# psu_testboard_v1_1_1.net
KiCad netlist of a schematic drawn in EAGLE
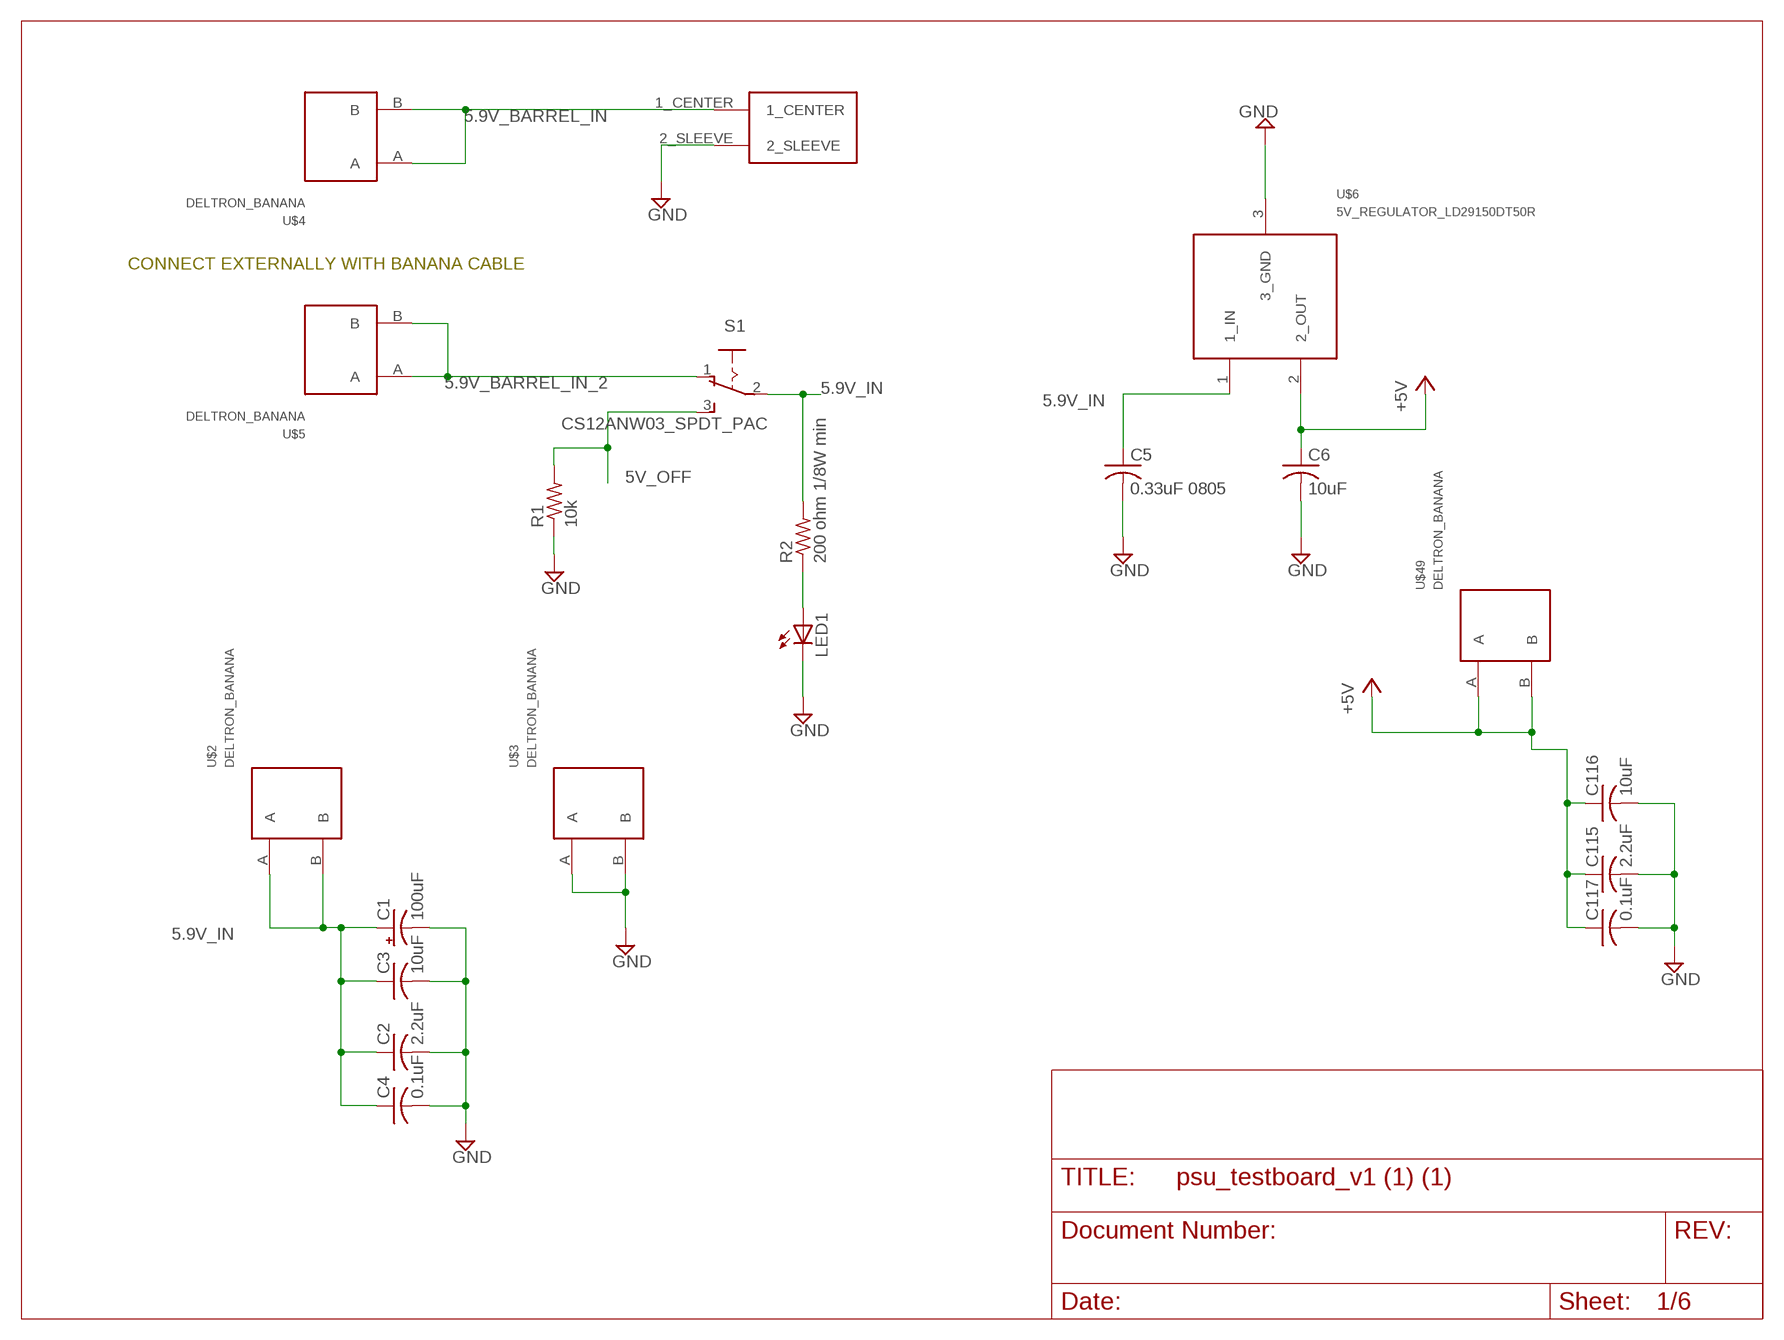
[diagram p0: schematic, sheet 1]
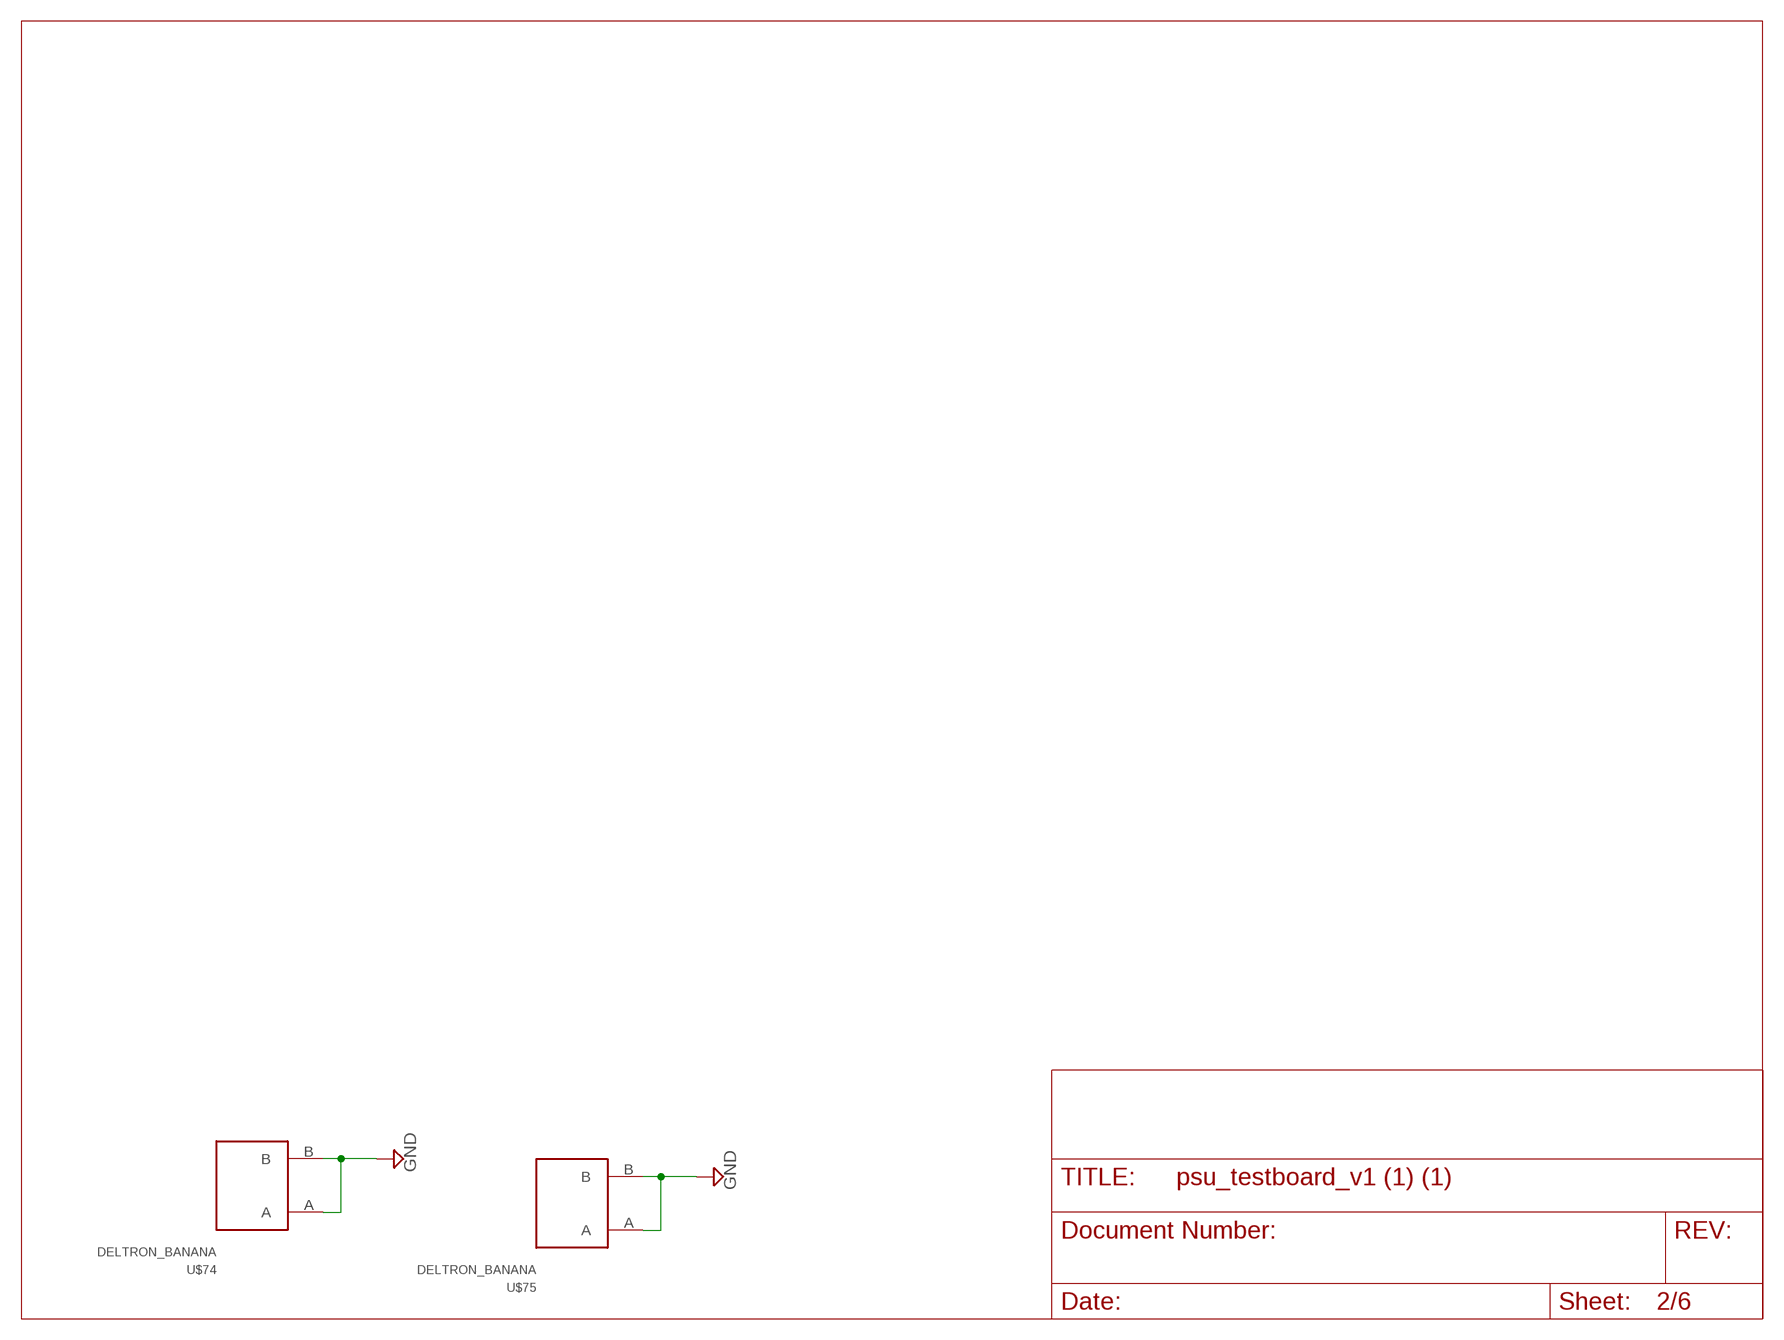
[diagram p1: schematic, sheet 2]
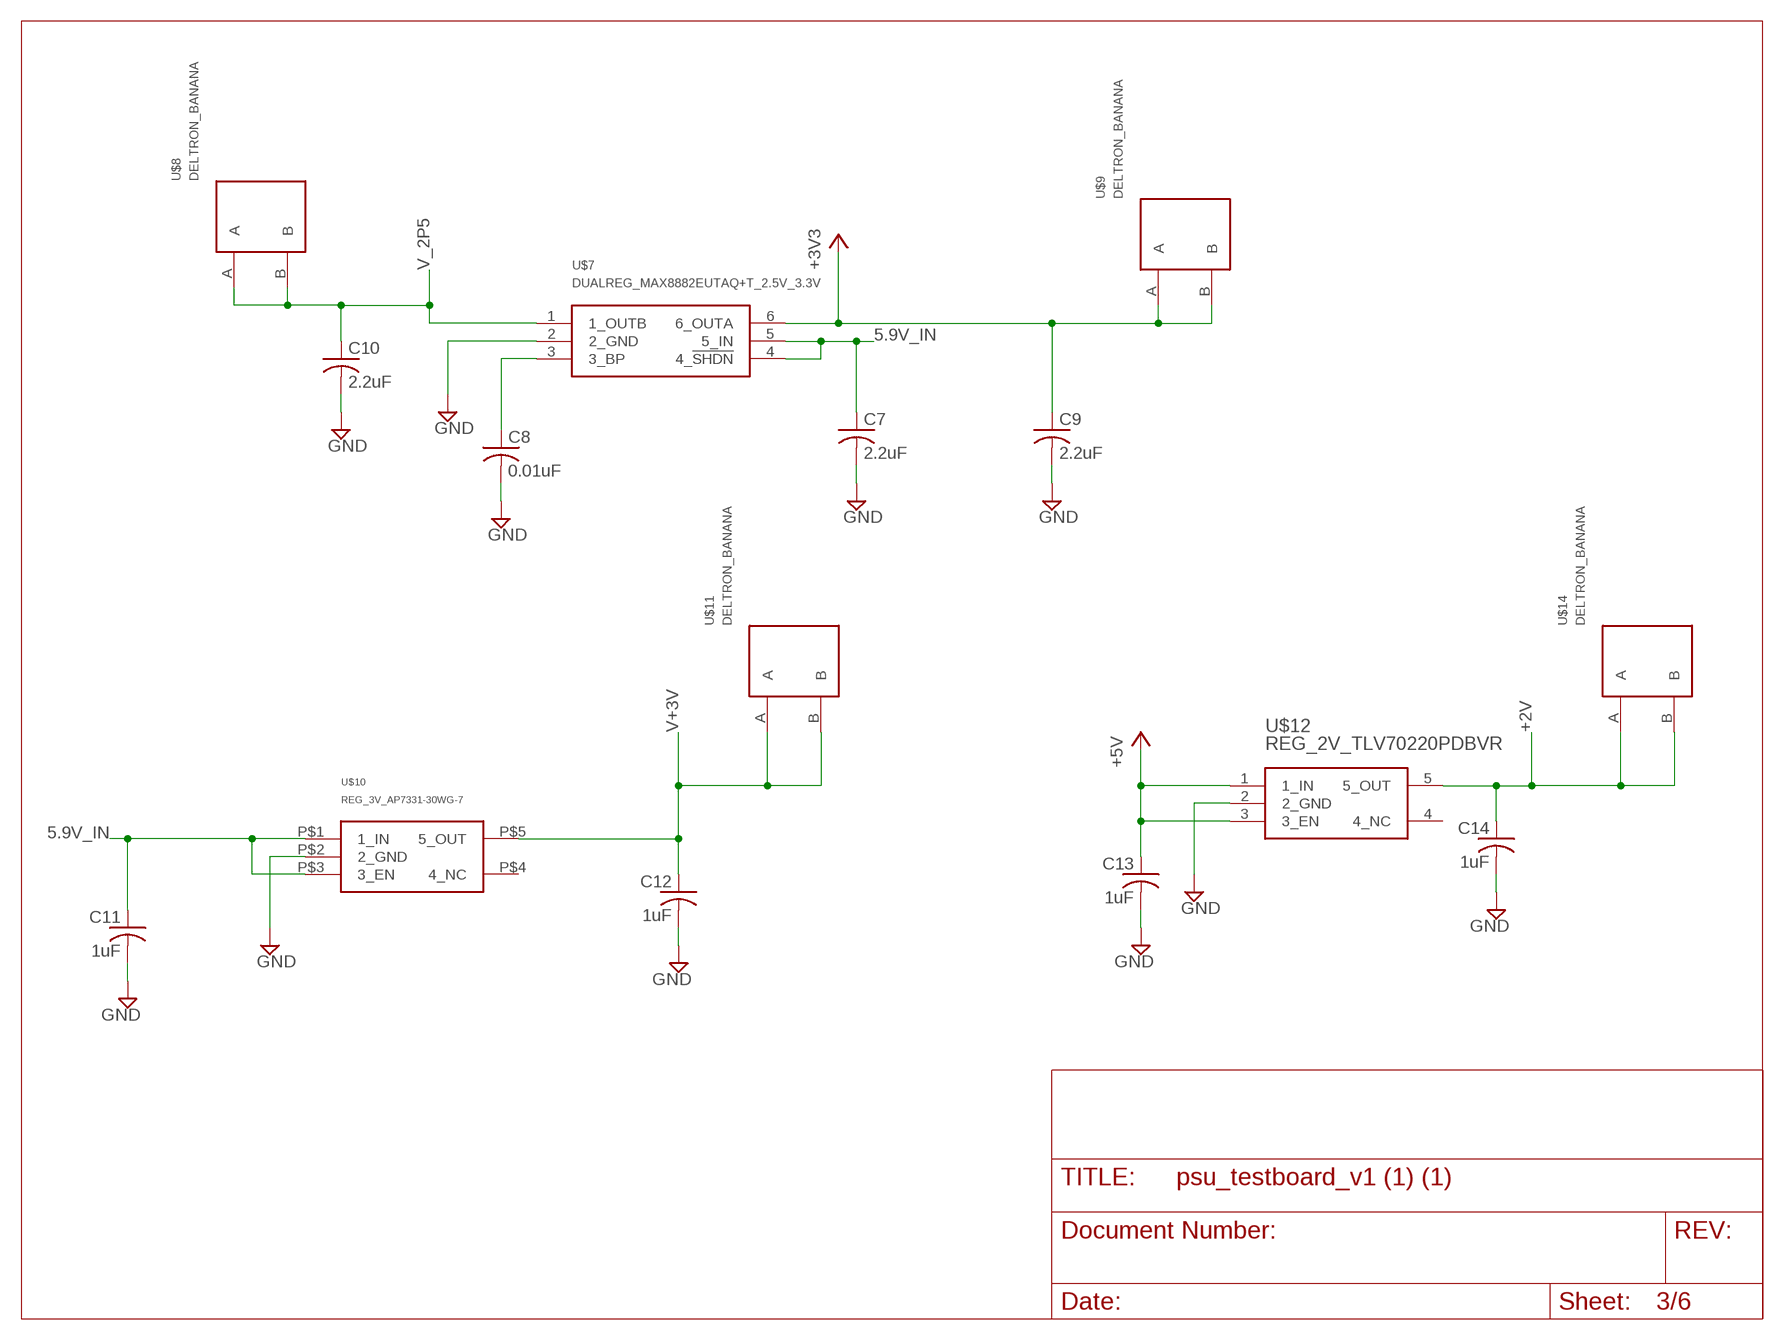
[diagram p2: schematic, sheet 3]
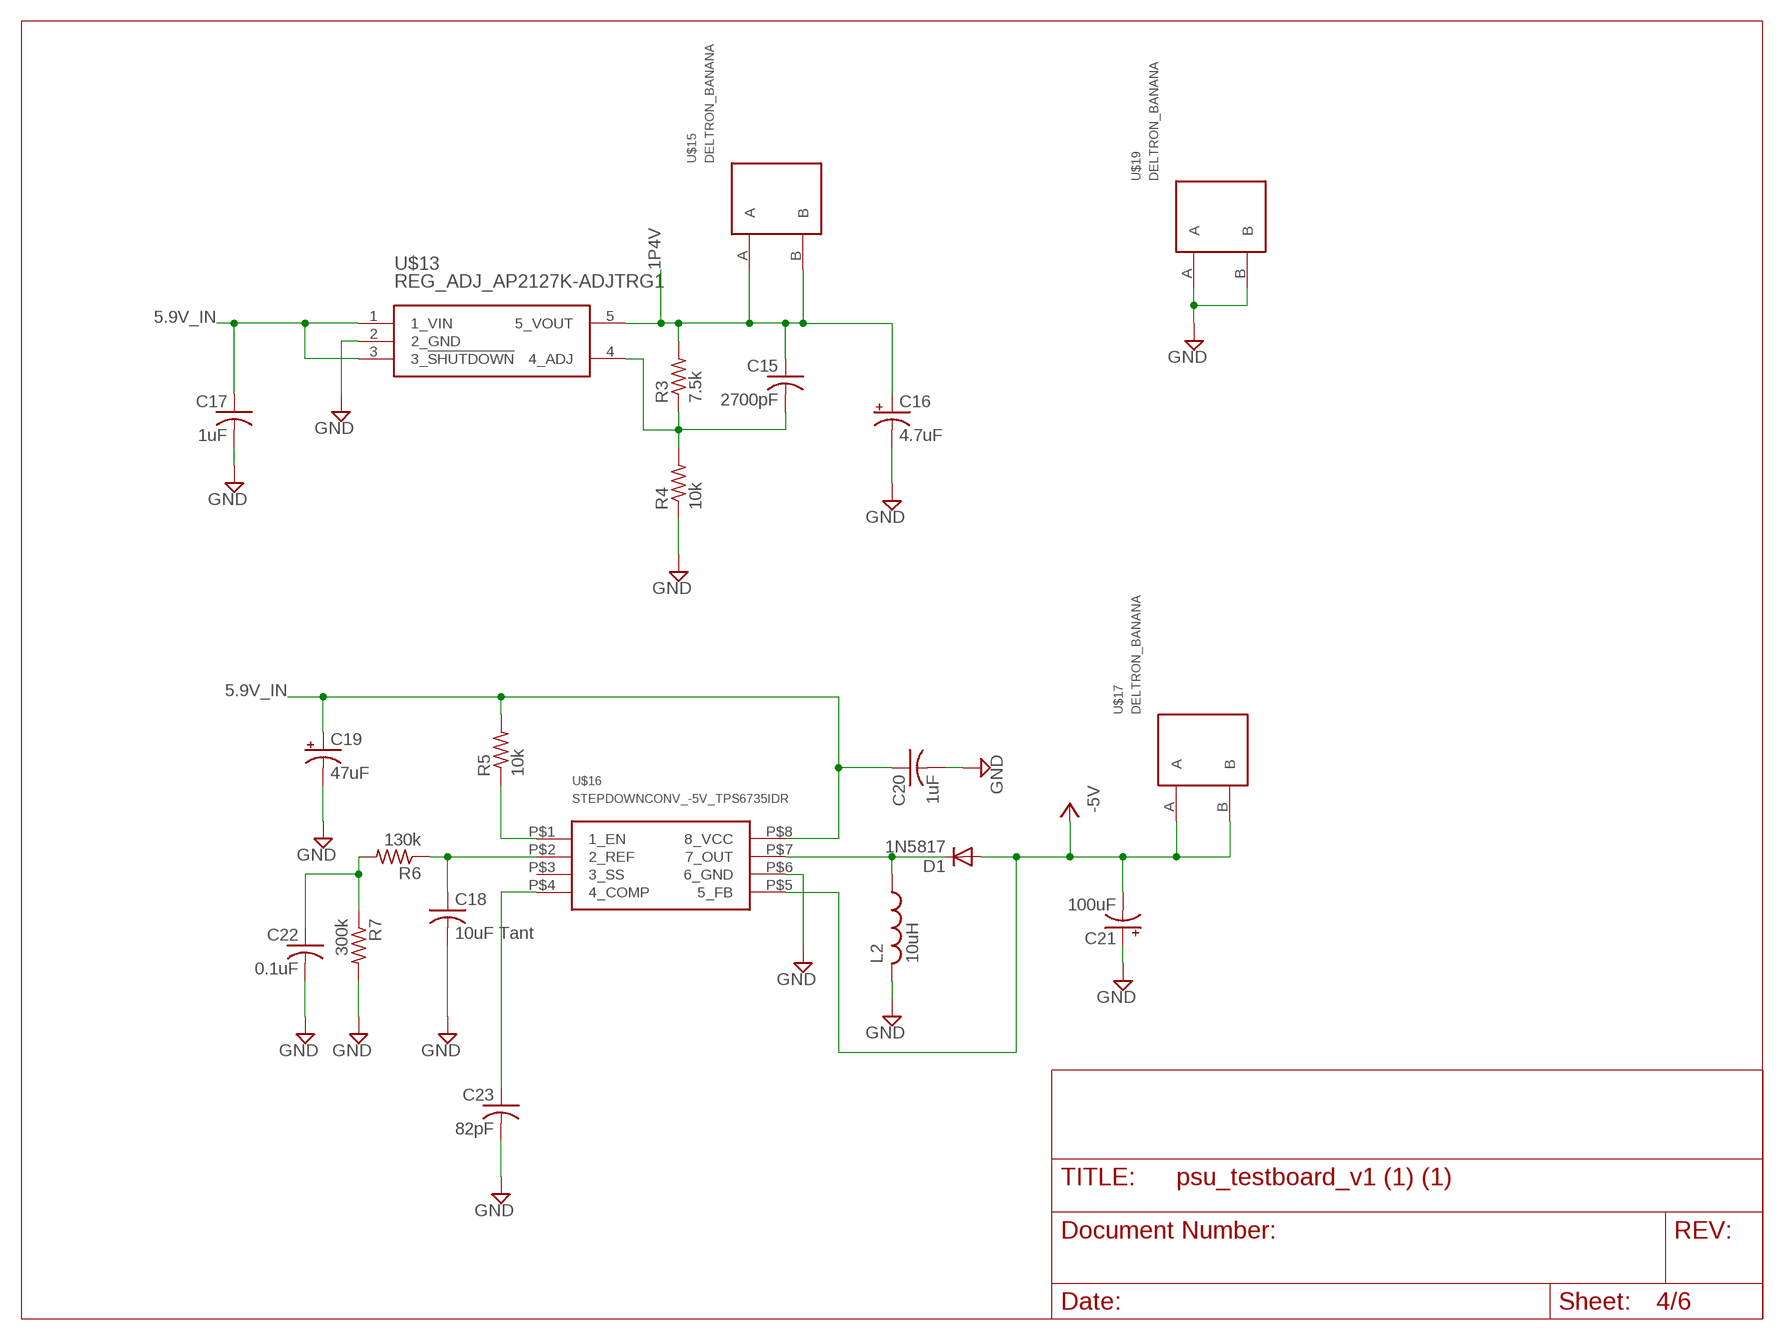
[diagram p3: schematic, sheet 4]
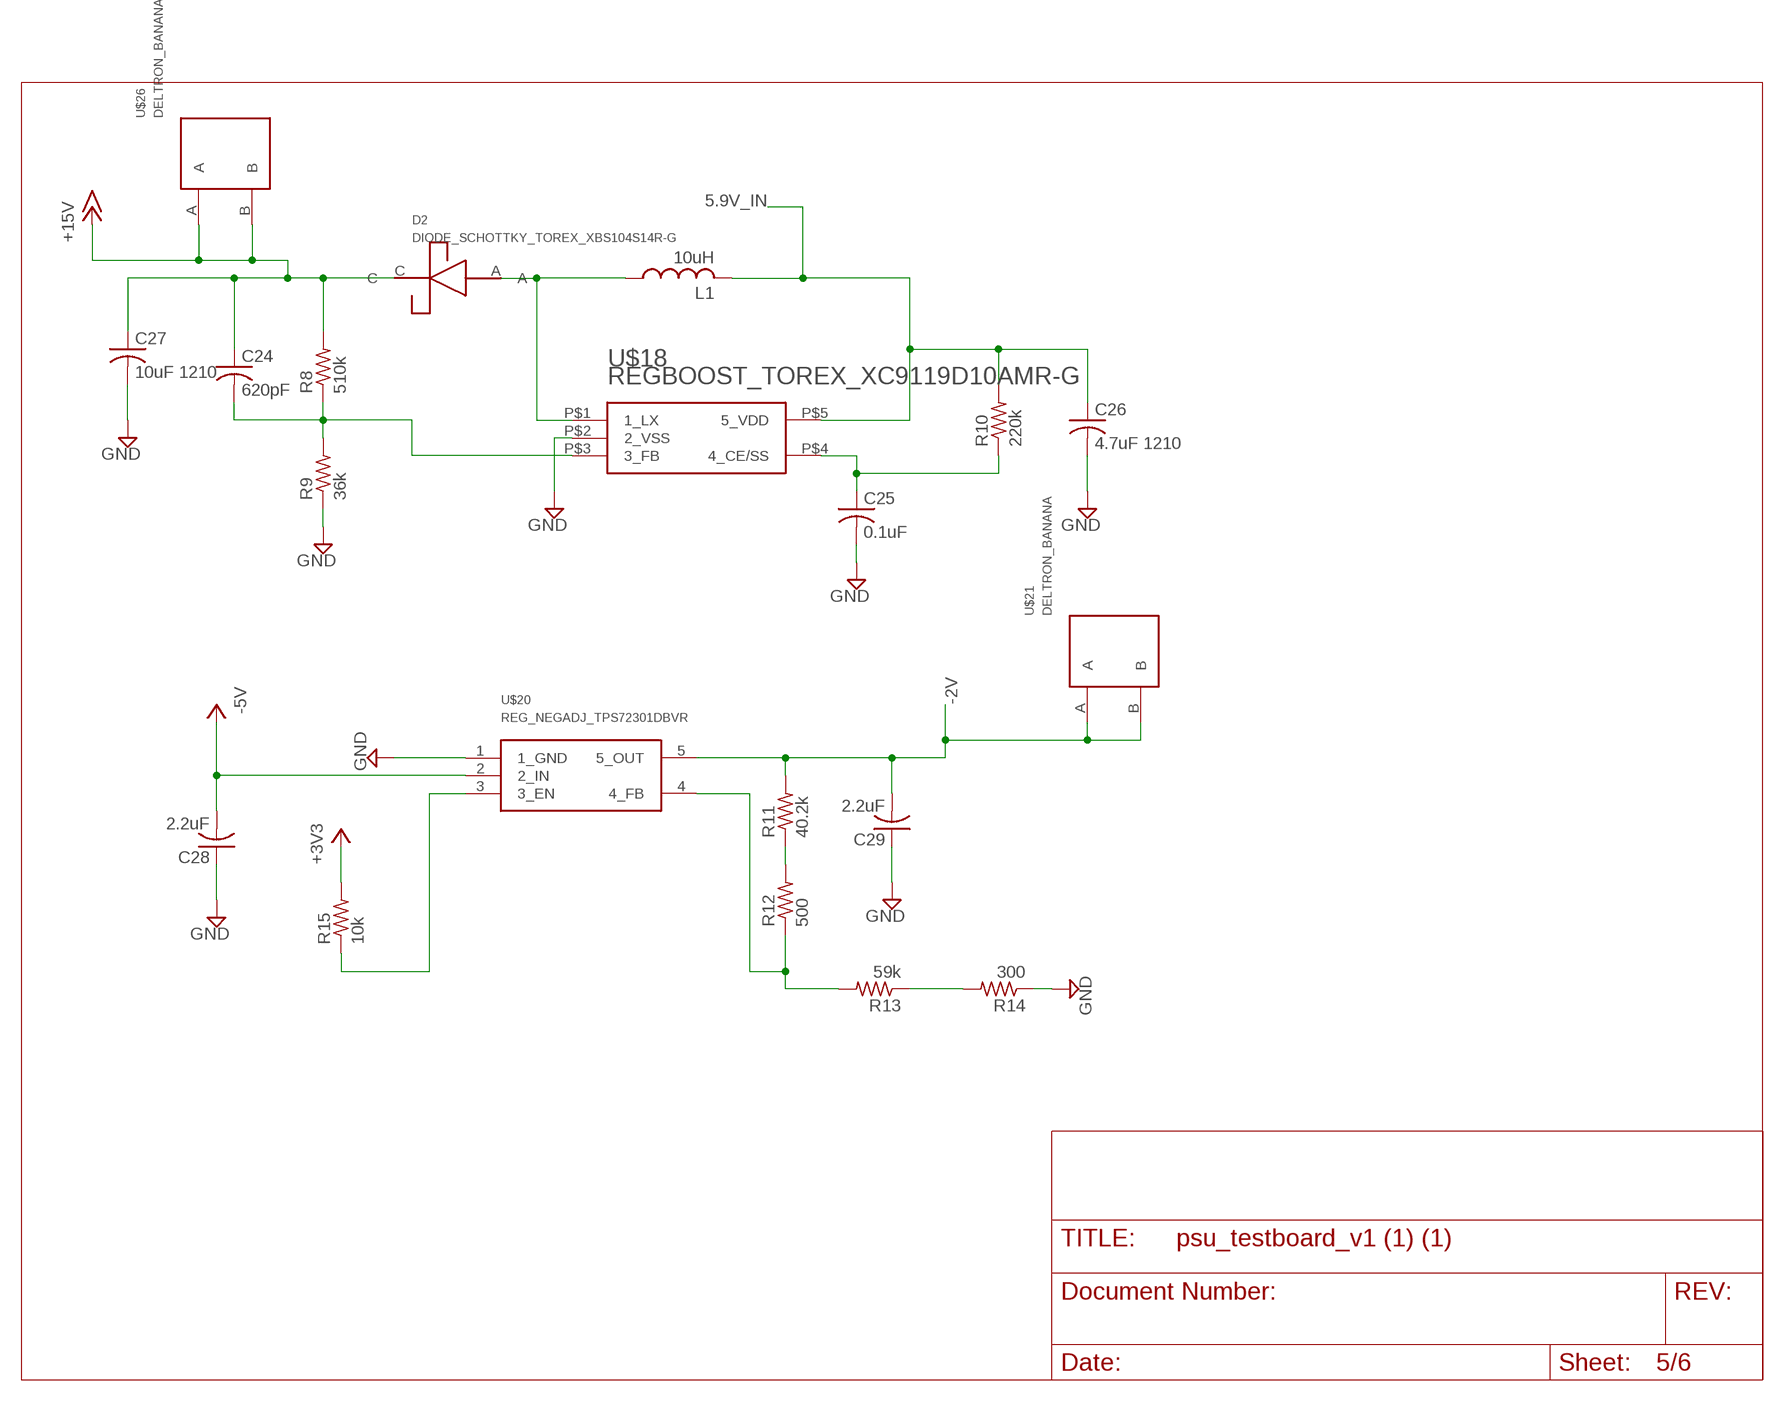
[diagram p4: schematic, sheet 5]
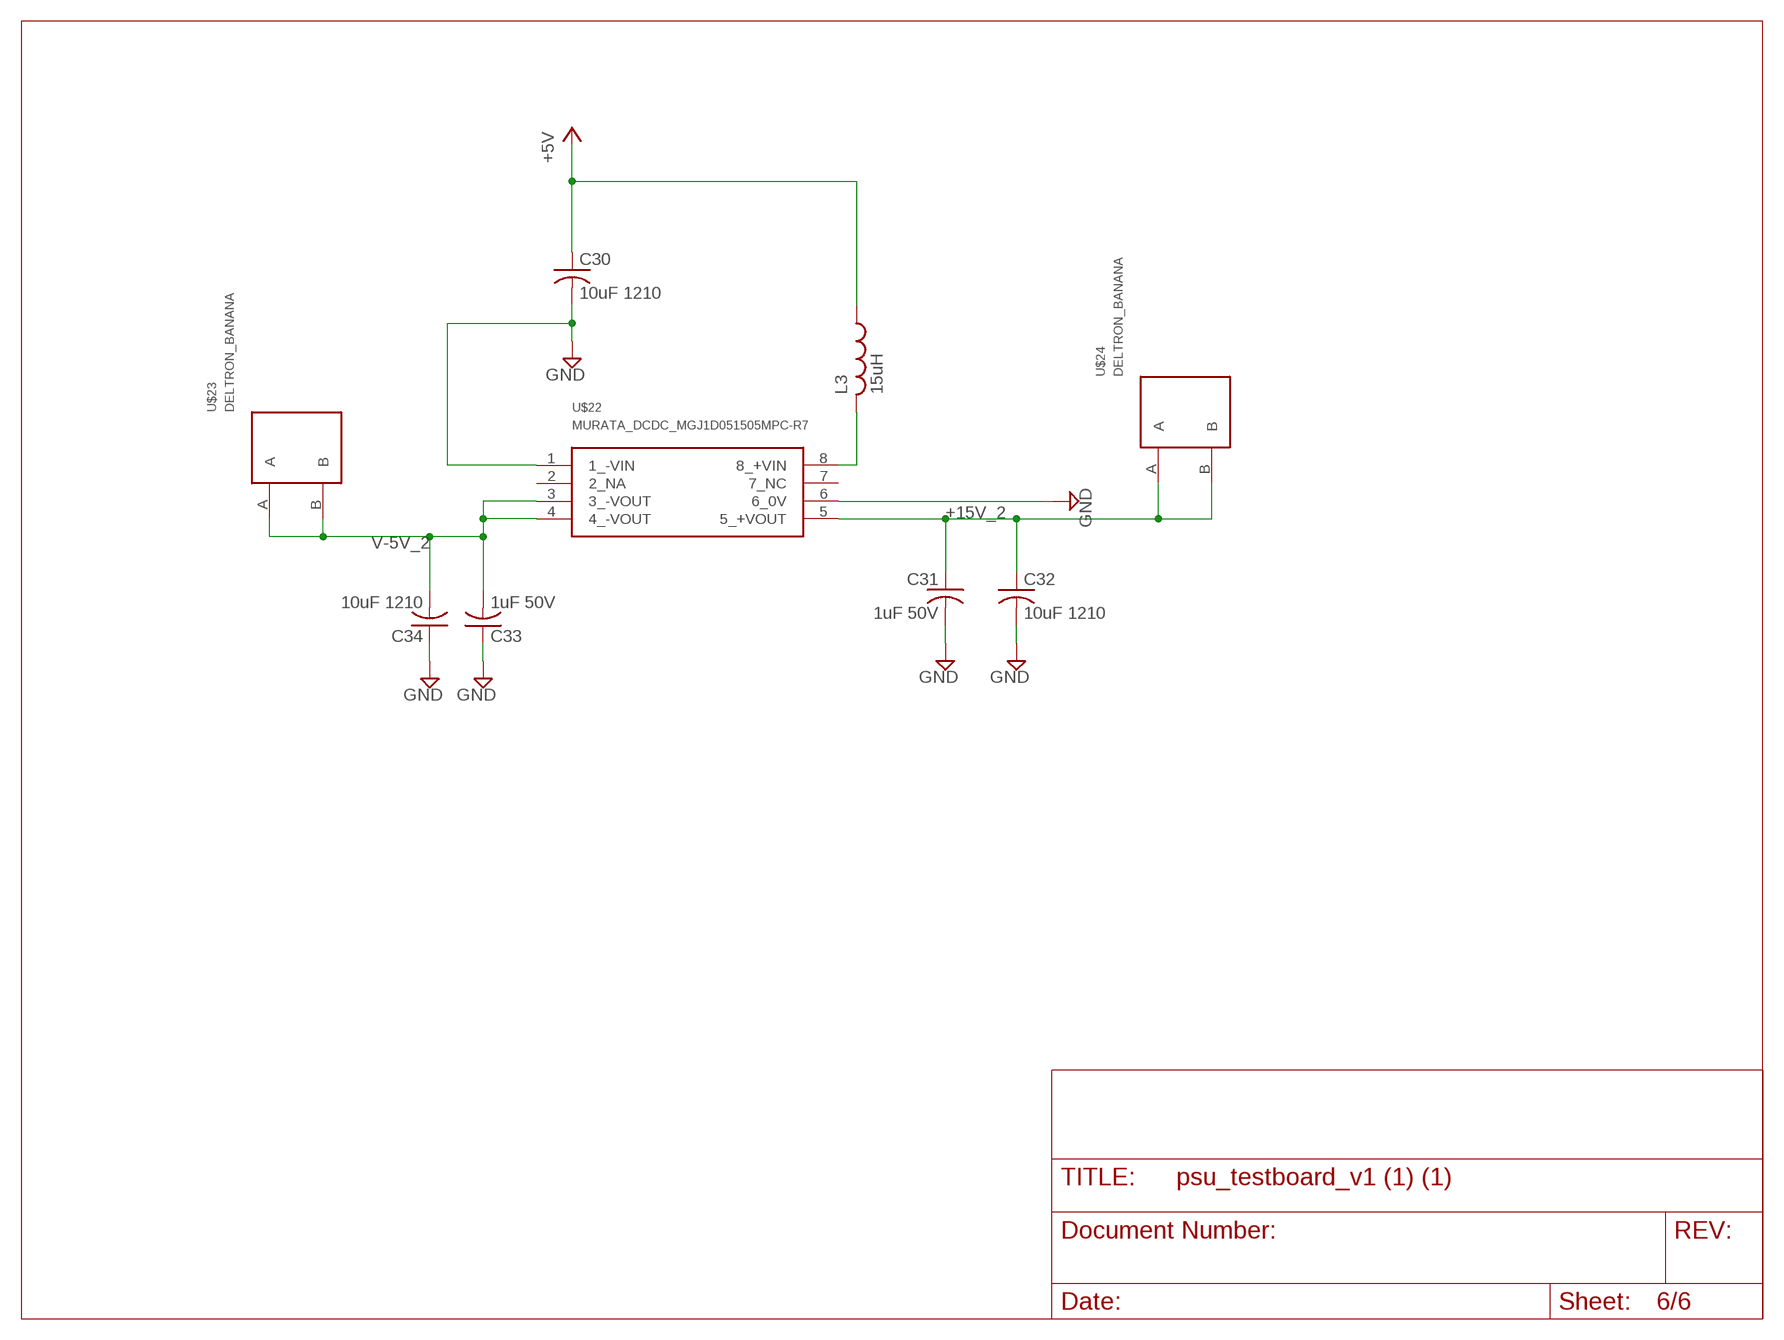
[diagram p5: schematic, sheet 6]

(export (version "E")
  (design (tool "Eeschema 10.0.6"))
  (components
    (comp (ref "C7")
      (value "2.2uF")
      (footprint "eagle-import:C0603")
      (libsource (lib "eagle-import") (part "C-USC0603"))
    )
    (comp (ref "C8")
      (value "0.01uF")
      (footprint "eagle-import:C0603")
      (libsource (lib "eagle-import") (part "C-USC0603"))
    )
    (comp (ref "C9")
      (value "2.2uF")
      (footprint "eagle-import:C0603")
      (libsource (lib "eagle-import") (part "C-USC0603"))
    )
    (comp (ref "C10")
      (value "2.2uF")
      (footprint "eagle-import:C0603")
      (libsource (lib "eagle-import") (part "C-USC0603"))
    )
    (comp (ref "C11")
      (value "1uF")
      (footprint "eagle-import:C0603")
      (libsource (lib "eagle-import") (part "C-USC0603"))
    )
    (comp (ref "C12")
      (value "1uF")
      (footprint "eagle-import:C0603")
      (libsource (lib "eagle-import") (part "C-USC0603"))
    )
    (comp (ref "C13")
      (value "1uF")
      (footprint "eagle-import:C0603")
      (libsource (lib "eagle-import") (part "C-USC0603"))
    )
    (comp (ref "C14")
      (value "1uF")
      (footprint "eagle-import:C0603")
      (libsource (lib "eagle-import") (part "C-USC0603"))
    )
    (comp (ref "U$7")
      (value "DUALREG_MAX8882EUTAQ+T_2.5V_3.3V")
      (footprint "eagle-import:SOT23-6")
      (libsource (lib "eagle-import") (part "DUALREG_MAX8882EUTAQ+T_2.5V_3.3V"))
    )
    (comp (ref "U$8")
      (value "DELTRON_BANANA")
      (footprint "eagle-import:DELTRON_BANANA")
      (libsource (lib "eagle-import") (part "DELTRON_BANANA"))
    )
    (comp (ref "U$9")
      (value "DELTRON_BANANA")
      (footprint "eagle-import:DELTRON_BANANA")
      (libsource (lib "eagle-import") (part "DELTRON_BANANA"))
    )
    (comp (ref "U$10")
      (value "REG_3V_AP7331-30WG-7")
      (footprint "eagle-import:SOT-25")
      (libsource (lib "eagle-import") (part "REG_3V_AP7331-30WG-7"))
    )
    (comp (ref "U$11")
      (value "DELTRON_BANANA")
      (footprint "eagle-import:DELTRON_BANANA")
      (libsource (lib "eagle-import") (part "DELTRON_BANANA"))
    )
    (comp (ref "U$12")
      (value "REG_2V_TLV70220PDBVR")
      (footprint "eagle-import:SOT23-5")
      (libsource (lib "eagle-import") (part "REG_2V_TLV70220PDBVR"))
    )
    (comp (ref "U$14")
      (value "DELTRON_BANANA")
      (footprint "eagle-import:DELTRON_BANANA")
      (libsource (lib "eagle-import") (part "DELTRON_BANANA"))
    )
    (comp (ref "C1")
      (value "100uF")
      (footprint "eagle-import:CAP_POL_RADIAL_8MM_3P5MMPAD")
      (libsource (lib "eagle-import") (part "CAP_POL_DEV"))
    )
    (comp (ref "C2")
      (value "2.2uF")
      (footprint "eagle-import:C0603")
      (libsource (lib "eagle-import") (part "C-USC0603"))
    )
    (comp (ref "C3")
      (value "10uF")
      (footprint "eagle-import:C1206")
      (libsource (lib "eagle-import") (part "C-USC1206"))
    )
    (comp (ref "C4")
      (value "0.1uF")
      (footprint "eagle-import:C0603")
      (libsource (lib "eagle-import") (part "C-USC0603"))
    )
    (comp (ref "C5")
      (value "0.33uF 0805")
      (footprint "eagle-import:C0805")
      (libsource (lib "eagle-import") (part "C-USC0805"))
    )
    (comp (ref "C6")
      (value "10uF")
      (footprint "eagle-import:5MM_SMT_ELECTROLYTICCAP_PANASONIC")
      (libsource (lib "eagle-import") (part "5MM_ELECTROLYTIC_SMT_CAP_EEE-1VA100SR"))
    )
    (comp (ref "C115")
      (value "2.2uF")
      (footprint "eagle-import:C0603")
      (libsource (lib "eagle-import") (part "C-USC0603"))
    )
    (comp (ref "C116")
      (value "10uF")
      (footprint "eagle-import:C1206")
      (libsource (lib "eagle-import") (part "C-USC1206"))
    )
    (comp (ref "C117")
      (value "0.1uF")
      (footprint "eagle-import:C0603")
      (libsource (lib "eagle-import") (part "C-USC0603"))
    )
    (comp (ref "LED1")
      (value "LED3MM")
      (footprint "eagle-import:LED3MM")
      (libsource (lib "eagle-import") (part "LED3MM"))
    )
    (comp (ref "R1")
      (value "10k")
      (footprint "eagle-import:R0603")
      (libsource (lib "eagle-import") (part "R-US_R0603"))
    )
    (comp (ref "R2")
      (value "200 ohm 1/8W min")
      (footprint "eagle-import:R0603")
      (libsource (lib "eagle-import") (part "R-US_R0603"))
    )
    (comp (ref "S1")
      (value "CS12ANW03_SPDT_PAC")
      (footprint "eagle-import:CS12ANW03_NKK_SPDT_SLIDESWITCH_PAC")
      (libsource (lib "eagle-import") (part "CS12ANW03_SPDT_PAC"))
    )
    (comp (ref "U$1")
      (value "BARREL_JACK_PJ-037A")
      (footprint "eagle-import:BARREL_JACK_PJ-037A")
      (libsource (lib "eagle-import") (part "BARREL_JACK_PJ-037A"))
    )
    (comp (ref "U$2")
      (value "DELTRON_BANANA")
      (footprint "eagle-import:DELTRON_BANANA")
      (libsource (lib "eagle-import") (part "DELTRON_BANANA"))
    )
    (comp (ref "U$3")
      (value "DELTRON_BANANA")
      (footprint "eagle-import:DELTRON_BANANA")
      (libsource (lib "eagle-import") (part "DELTRON_BANANA"))
    )
    (comp (ref "U$4")
      (value "DELTRON_BANANA")
      (footprint "eagle-import:DELTRON_BANANA")
      (libsource (lib "eagle-import") (part "DELTRON_BANANA"))
    )
    (comp (ref "U$5")
      (value "DELTRON_BANANA")
      (footprint "eagle-import:DELTRON_BANANA")
      (libsource (lib "eagle-import") (part "DELTRON_BANANA"))
    )
    (comp (ref "U$6")
      (value "5V_REGULATOR_LD29150DT50R")
      (footprint "eagle-import:DPAK")
      (libsource (lib "eagle-import") (part "5V_REGULATOR_LD29150DT50R"))
    )
    (comp (ref "U$49")
      (value "DELTRON_BANANA")
      (footprint "eagle-import:DELTRON_BANANA")
      (libsource (lib "eagle-import") (part "DELTRON_BANANA"))
    )
    (comp (ref "C24")
      (value "620pF")
      (footprint "eagle-import:C0603")
      (libsource (lib "eagle-import") (part "C-USC0603"))
    )
    (comp (ref "C25")
      (value "0.1uF")
      (footprint "eagle-import:C0603")
      (libsource (lib "eagle-import") (part "C-USC0603"))
    )
    (comp (ref "C26")
      (value "4.7uF 1210")
      (footprint "eagle-import:C1210")
      (libsource (lib "eagle-import") (part "C-USC1210"))
    )
    (comp (ref "C27")
      (value "10uF 1210")
      (footprint "eagle-import:C1210")
      (libsource (lib "eagle-import") (part "C-USC1210"))
    )
    (comp (ref "C28")
      (value "2.2uF")
      (footprint "eagle-import:C0603")
      (libsource (lib "eagle-import") (part "C-USC0603"))
    )
    (comp (ref "C29")
      (value "2.2uF")
      (footprint "eagle-import:C0603")
      (libsource (lib "eagle-import") (part "C-USC0603"))
    )
    (comp (ref "D2")
      (value "DIODE_SCHOTTKY_TOREX_XBS104S14R-G")
      (footprint "eagle-import:SOD-123A")
      (libsource (lib "eagle-import") (part "DIODE_SCHOTTKY_TOREX_XBS104S14R-G"))
    )
    (comp (ref "L1")
      (value "10uH")
      (footprint "eagle-import:SUMIDA_INDUCTOR_CDRH4D18CNP-100PC")
      (libsource (lib "eagle-import") (part "SUMIDA_10UH_IND_CDRH4D18CNP-100PC"))
    )
    (comp (ref "R8")
      (value "510k")
      (footprint "eagle-import:R0603")
      (libsource (lib "eagle-import") (part "R-US_R0603"))
    )
    (comp (ref "R9")
      (value "36k")
      (footprint "eagle-import:R0603")
      (libsource (lib "eagle-import") (part "R-US_R0603"))
    )
    (comp (ref "R10")
      (value "220k")
      (footprint "eagle-import:R0603")
      (libsource (lib "eagle-import") (part "R-US_R0603"))
    )
    (comp (ref "R11")
      (value "40.2k")
      (footprint "eagle-import:R0603")
      (libsource (lib "eagle-import") (part "R-US_R0603"))
    )
    (comp (ref "R12")
      (value "500")
      (footprint "eagle-import:R0603")
      (libsource (lib "eagle-import") (part "R-US_R0603"))
    )
    (comp (ref "R13")
      (value "59k")
      (footprint "eagle-import:R0603")
      (libsource (lib "eagle-import") (part "R-US_R0603"))
    )
    (comp (ref "R14")
      (value "300")
      (footprint "eagle-import:R0603")
      (libsource (lib "eagle-import") (part "R-US_R0603"))
    )
    (comp (ref "R15")
      (value "10k")
      (footprint "eagle-import:R0603")
      (libsource (lib "eagle-import") (part "R-US_R0603"))
    )
    (comp (ref "U$18")
      (value "REGBOOST_TOREX_XC9119D10AMR-G")
      (footprint "eagle-import:SOT25-5")
      (libsource (lib "eagle-import") (part "REGBOOST_TOREX_XC9119D10AMR-G"))
    )
    (comp (ref "U$20")
      (value "REG_NEGADJ_TPS72301DBVR")
      (footprint "eagle-import:SOT23-5")
      (libsource (lib "eagle-import") (part "REG_NEGADJ_TPS72301DBVR"))
    )
    (comp (ref "U$21")
      (value "DELTRON_BANANA")
      (footprint "eagle-import:DELTRON_BANANA")
      (libsource (lib "eagle-import") (part "DELTRON_BANANA"))
    )
    (comp (ref "U$26")
      (value "DELTRON_BANANA")
      (footprint "eagle-import:DELTRON_BANANA")
      (libsource (lib "eagle-import") (part "DELTRON_BANANA"))
    )
    (comp (ref "U$74")
      (value "DELTRON_BANANA")
      (footprint "eagle-import:DELTRON_BANANA")
      (libsource (lib "eagle-import") (part "DELTRON_BANANA"))
    )
    (comp (ref "U$75")
      (value "DELTRON_BANANA")
      (footprint "eagle-import:DELTRON_BANANA")
      (libsource (lib "eagle-import") (part "DELTRON_BANANA"))
    )
    (comp (ref "C30")
      (value "10uF 1210")
      (footprint "eagle-import:C1210")
      (libsource (lib "eagle-import") (part "C-USC1210"))
    )
    (comp (ref "C31")
      (value "1uF 50V")
      (footprint "eagle-import:C0603")
      (libsource (lib "eagle-import") (part "C-USC0603"))
    )
    (comp (ref "C32")
      (value "10uF 1210")
      (footprint "eagle-import:C1210")
      (libsource (lib "eagle-import") (part "C-USC1210"))
    )
    (comp (ref "C33")
      (value "1uF 50V")
      (footprint "eagle-import:C0603")
      (libsource (lib "eagle-import") (part "C-USC0603"))
    )
    (comp (ref "C34")
      (value "10uF 1210")
      (footprint "eagle-import:C1210")
      (libsource (lib "eagle-import") (part "C-USC1210"))
    )
    (comp (ref "L3")
      (value "15uH")
      (footprint "eagle-import:0207_5V")
      (libsource (lib "eagle-import") (part "L-US0207/5V"))
    )
    (comp (ref "U$22")
      (value "MURATA_DCDC_MGJ1D051505MPC-R7")
      (footprint "eagle-import:MURATA_DCDC_MGJ1D051505MPC-R7")
      (libsource (lib "eagle-import") (part "MURATA_DCDC_MGJ1D051505MPC-R7"))
    )
    (comp (ref "U$23")
      (value "DELTRON_BANANA")
      (footprint "eagle-import:DELTRON_BANANA")
      (libsource (lib "eagle-import") (part "DELTRON_BANANA"))
    )
    (comp (ref "U$24")
      (value "DELTRON_BANANA")
      (footprint "eagle-import:DELTRON_BANANA")
      (libsource (lib "eagle-import") (part "DELTRON_BANANA"))
    )
    (comp (ref "C15")
      (value "2700pF")
      (footprint "eagle-import:C0603")
      (libsource (lib "eagle-import") (part "C-USC0603"))
    )
    (comp (ref "C16")
      (value "4.7uF")
      (footprint "eagle-import:E2,5RE")
      (libsource (lib "eagle-import") (part "CPOL-USE2.5-4V"))
    )
    (comp (ref "C17")
      (value "1uF")
      (footprint "eagle-import:C0603")
      (libsource (lib "eagle-import") (part "C-USC0603"))
    )
    (comp (ref "C18")
      (value "10uF Tant")
      (footprint "eagle-import:C1206")
      (libsource (lib "eagle-import") (part "C-USC1206"))
    )
    (comp (ref "C19")
      (value "47uF")
      (footprint "eagle-import:E5-10,5")
      (libsource (lib "eagle-import") (part "CPOL-USE5-10.5"))
    )
    (comp (ref "C20")
      (value "1uF")
      (footprint "eagle-import:C0603")
      (libsource (lib "eagle-import") (part "C-USC0603"))
    )
    (comp (ref "C21")
      (value "100uF")
      (footprint "eagle-import:E2,5-7")
      (libsource (lib "eagle-import") (part "CPOL-USE2.5-7"))
    )
    (comp (ref "C22")
      (value "0.1uF")
      (footprint "eagle-import:C0603")
      (libsource (lib "eagle-import") (part "C-USC0603"))
    )
    (comp (ref "C23")
      (value "82pF")
      (footprint "eagle-import:C0603")
      (libsource (lib "eagle-import") (part "C-USC0603"))
    )
    (comp (ref "D1")
      (value "1N5817")
      (footprint "eagle-import:DIODE-1N4148")
      (libsource (lib "eagle-import") (part "DIODE1N4148"))
    )
    (comp (ref "L2")
      (value "10uH")
      (footprint "eagle-import:COILCRAFT_POWERIND_DO1608C-103MLB")
      (libsource (lib "eagle-import") (part "COILCRAFT_10UHIND_DO1608C-103MLB"))
    )
    (comp (ref "R3")
      (value "7.5k")
      (footprint "eagle-import:R0603")
      (libsource (lib "eagle-import") (part "R-US_R0603"))
    )
    (comp (ref "R4")
      (value "10k")
      (footprint "eagle-import:R0603")
      (libsource (lib "eagle-import") (part "R-US_R0603"))
    )
    (comp (ref "R5")
      (value "10k")
      (footprint "eagle-import:R0603")
      (libsource (lib "eagle-import") (part "R-US_R0603"))
    )
    (comp (ref "R6")
      (value "130k")
      (footprint "eagle-import:R0603")
      (libsource (lib "eagle-import") (part "R-US_R0603"))
    )
    (comp (ref "R7")
      (value "300k")
      (footprint "eagle-import:R0603")
      (libsource (lib "eagle-import") (part "R-US_R0603"))
    )
    (comp (ref "U$13")
      (value "REG_ADJ_AP2127K-ADJTRG1")
      (footprint "eagle-import:SOT23-5")
      (libsource (lib "eagle-import") (part "REG_ADJ_AP2127K-ADJTRG1"))
    )
    (comp (ref "U$15")
      (value "DELTRON_BANANA")
      (footprint "eagle-import:DELTRON_BANANA")
      (libsource (lib "eagle-import") (part "DELTRON_BANANA"))
    )
    (comp (ref "U$16")
      (value "STEPDOWNCONV_-5V_TPS6735IDR")
      (footprint "eagle-import:SOIC8")
      (libsource (lib "eagle-import") (part "STEPDOWNCONV_-5V_TPS6735IDR"))
    )
    (comp (ref "U$17")
      (value "DELTRON_BANANA")
      (footprint "eagle-import:DELTRON_BANANA")
      (libsource (lib "eagle-import") (part "DELTRON_BANANA"))
    )
    (comp (ref "U$19")
      (value "DELTRON_BANANA")
      (footprint "eagle-import:DELTRON_BANANA")
      (libsource (lib "eagle-import") (part "DELTRON_BANANA"))
    )
  )
  (nets
    (net (code "1") (name "+2V") (class "Default")
      (node (ref "C14") (pin "1") (pinfunction "1_1") (pintype "passive"))
      (node (ref "U$12") (pin "5") (pinfunction "5_OUT_5") (pintype "bidirectional"))
      (node (ref "U$14") (pin "A") (pinfunction "A_A") (pintype "bidirectional"))
      (node (ref "U$14") (pin "B") (pinfunction "B_B") (pintype "bidirectional"))
    )
    (net (code "2") (name "+3V3") (class "Default")
      (node (ref "C9") (pin "1") (pinfunction "1_1") (pintype "passive"))
      (node (ref "R15") (pin "2") (pinfunction "2_2") (pintype "passive"))
      (node (ref "U$7") (pin "6") (pinfunction "6_OUTA_6") (pintype "bidirectional"))
      (node (ref "U$9") (pin "A") (pinfunction "A_A") (pintype "bidirectional"))
      (node (ref "U$9") (pin "B") (pinfunction "B_B") (pintype "bidirectional"))
    )
    (net (code "3") (name "+5V") (class "Default")
      (node (ref "C115") (pin "1") (pinfunction "1_1") (pintype "passive"))
      (node (ref "C116") (pin "1") (pinfunction "1_1") (pintype "passive"))
      (node (ref "C117") (pin "1") (pinfunction "1_1") (pintype "passive"))
      (node (ref "C13") (pin "1") (pinfunction "1_1") (pintype "passive"))
      (node (ref "C30") (pin "1") (pinfunction "1_1") (pintype "passive"))
      (node (ref "C6") (pin "1+") (pinfunction "1_1+") (pintype "passive"))
      (node (ref "L3") (pin "1") (pinfunction "1_1") (pintype "passive"))
      (node (ref "U$12") (pin "1") (pinfunction "1_IN_1") (pintype "bidirectional"))
      (node (ref "U$12") (pin "3") (pinfunction "3_EN_3") (pintype "bidirectional"))
      (node (ref "U$49") (pin "A") (pinfunction "A_A") (pintype "bidirectional"))
      (node (ref "U$49") (pin "B") (pinfunction "B_B") (pintype "bidirectional"))
      (node (ref "U$6") (pin "2") (pinfunction "2_OUT_2") (pintype "bidirectional"))
    )
    (net (code "4") (name "+15V") (class "Default")
      (node (ref "C24") (pin "1") (pinfunction "1_1") (pintype "passive"))
      (node (ref "C27") (pin "1") (pinfunction "1_1") (pintype "passive"))
      (node (ref "D2") (pin "C") (pinfunction "C_C") (pintype "bidirectional"))
      (node (ref "R8") (pin "2") (pinfunction "2_2") (pintype "passive"))
      (node (ref "U$26") (pin "A") (pinfunction "A_A") (pintype "bidirectional"))
      (node (ref "U$26") (pin "B") (pinfunction "B_B") (pintype "bidirectional"))
    )
    (net (code "5") (name "+15V_2") (class "Default")
      (node (ref "C31") (pin "1") (pinfunction "1_1") (pintype "passive"))
      (node (ref "C32") (pin "1") (pinfunction "1_1") (pintype "passive"))
      (node (ref "U$22") (pin "5") (pinfunction "5_+VOUT_5") (pintype "bidirectional"))
      (node (ref "U$24") (pin "A") (pinfunction "A_A") (pintype "bidirectional"))
      (node (ref "U$24") (pin "B") (pinfunction "B_B") (pintype "bidirectional"))
    )
    (net (code "6") (name "-2V") (class "Default")
      (node (ref "C29") (pin "2") (pinfunction "2_2") (pintype "passive"))
      (node (ref "R11") (pin "2") (pinfunction "2_2") (pintype "passive"))
      (node (ref "U$20") (pin "5") (pinfunction "5_OUT_5") (pintype "bidirectional"))
      (node (ref "U$21") (pin "A") (pinfunction "A_A") (pintype "bidirectional"))
      (node (ref "U$21") (pin "B") (pinfunction "B_B") (pintype "bidirectional"))
    )
    (net (code "7") (name "-5V") (class "Default")
      (node (ref "C21") (pin "-") (pinfunction "-_-") (pintype "passive"))
      (node (ref "C28") (pin "2") (pinfunction "2_2") (pintype "passive"))
      (node (ref "D1") (pin "A") (pinfunction "A_A") (pintype "passive"))
      (node (ref "U$16") (pin "P$5") (pinfunction "5_FB_P$5") (pintype "bidirectional"))
      (node (ref "U$17") (pin "A") (pinfunction "A_A") (pintype "bidirectional"))
      (node (ref "U$17") (pin "B") (pinfunction "B_B") (pintype "bidirectional"))
      (node (ref "U$20") (pin "2") (pinfunction "2_IN_2") (pintype "bidirectional"))
    )
    (net (code "8") (name "1P4V") (class "Default")
      (node (ref "C15") (pin "1") (pinfunction "1_1") (pintype "passive"))
      (node (ref "C16") (pin "+") (pinfunction "+_+") (pintype "passive"))
      (node (ref "R3") (pin "2") (pinfunction "2_2") (pintype "passive"))
      (node (ref "U$13") (pin "5") (pinfunction "5_VOUT_5") (pintype "bidirectional"))
      (node (ref "U$15") (pin "A") (pinfunction "A_A") (pintype "bidirectional"))
      (node (ref "U$15") (pin "B") (pinfunction "B_B") (pintype "bidirectional"))
    )
    (net (code "9") (name "5.9V_BARREL_IN") (class "Default")
      (node (ref "U$1") (pin "1_CENTER") (pinfunction "1_CENTER_1_CENTER") (pintype "bidirectional"))
      (node (ref "U$4") (pin "A") (pinfunction "A_A") (pintype "bidirectional"))
      (node (ref "U$4") (pin "B") (pinfunction "B_B") (pintype "bidirectional"))
    )
    (net (code "10") (name "5.9V_BARREL_IN_2") (class "Default")
      (node (ref "S1") (pin "1") (pinfunction "1_1") (pintype "passive"))
      (node (ref "U$5") (pin "A") (pinfunction "A_A") (pintype "bidirectional"))
      (node (ref "U$5") (pin "B") (pinfunction "B_B") (pintype "bidirectional"))
    )
    (net (code "11") (name "5.9V_IN") (class "Default")
      (node (ref "C1") (pin "PIN+") (pinfunction "PIN+_PIN+") (pintype "passive"))
      (node (ref "C11") (pin "1") (pinfunction "1_1") (pintype "passive"))
      (node (ref "C17") (pin "1") (pinfunction "1_1") (pintype "passive"))
      (node (ref "C19") (pin "+") (pinfunction "+_+") (pintype "passive"))
      (node (ref "C2") (pin "1") (pinfunction "1_1") (pintype "passive"))
      (node (ref "C20") (pin "1") (pinfunction "1_1") (pintype "passive"))
      (node (ref "C26") (pin "1") (pinfunction "1_1") (pintype "passive"))
      (node (ref "C3") (pin "1") (pinfunction "1_1") (pintype "passive"))
      (node (ref "C4") (pin "1") (pinfunction "1_1") (pintype "passive"))
      (node (ref "C5") (pin "1") (pinfunction "1_1") (pintype "passive"))
      (node (ref "C7") (pin "1") (pinfunction "1_1") (pintype "passive"))
      (node (ref "L1") (pin "P$2") (pinfunction "2_P$2") (pintype "passive"))
      (node (ref "R10") (pin "2") (pinfunction "2_2") (pintype "passive"))
      (node (ref "R2") (pin "2") (pinfunction "2_2") (pintype "passive"))
      (node (ref "R5") (pin "2") (pinfunction "2_2") (pintype "passive"))
      (node (ref "S1") (pin "2") (pinfunction "2_2") (pintype "passive"))
      (node (ref "U$10") (pin "P$1") (pinfunction "1_IN_P$1") (pintype "bidirectional"))
      (node (ref "U$10") (pin "P$3") (pinfunction "3_EN_P$3") (pintype "bidirectional"))
      (node (ref "U$13") (pin "1") (pinfunction "1_VIN_1") (pintype "bidirectional"))
      (node (ref "U$13") (pin "3") (pinfunction "3_~{SHUTDOWN}_3") (pintype "bidirectional"))
      (node (ref "U$16") (pin "P$8") (pinfunction "8_VCC_P$8") (pintype "bidirectional"))
      (node (ref "U$18") (pin "P$5") (pinfunction "5_VDD_P$5") (pintype "bidirectional"))
      (node (ref "U$2") (pin "A") (pinfunction "A_A") (pintype "bidirectional"))
      (node (ref "U$2") (pin "B") (pinfunction "B_B") (pintype "bidirectional"))
      (node (ref "U$6") (pin "1") (pinfunction "1_IN_1") (pintype "bidirectional"))
      (node (ref "U$7") (pin "4") (pinfunction "4_~{SHDN}_4") (pintype "bidirectional"))
      (node (ref "U$7") (pin "5") (pinfunction "5_IN_5") (pintype "bidirectional"))
    )
    (net (code "12") (name "5V_OFF") (class "Default")
      (node (ref "R1") (pin "2") (pinfunction "2_2") (pintype "passive"))
      (node (ref "S1") (pin "3") (pinfunction "3_3") (pintype "passive"))
    )
    (net (code "13") (name "GND") (class "Default")
      (node (ref "C1") (pin "PIN-") (pinfunction "PIN-_PIN-") (pintype "passive"))
      (node (ref "C10") (pin "2") (pinfunction "2_2") (pintype "passive"))
      (node (ref "C11") (pin "2") (pinfunction "2_2") (pintype "passive"))
      (node (ref "C115") (pin "2") (pinfunction "2_2") (pintype "passive"))
      (node (ref "C116") (pin "2") (pinfunction "2_2") (pintype "passive"))
      (node (ref "C117") (pin "2") (pinfunction "2_2") (pintype "passive"))
      (node (ref "C12") (pin "2") (pinfunction "2_2") (pintype "passive"))
      (node (ref "C13") (pin "2") (pinfunction "2_2") (pintype "passive"))
      (node (ref "C14") (pin "2") (pinfunction "2_2") (pintype "passive"))
      (node (ref "C16") (pin "-") (pinfunction "-_-") (pintype "passive"))
      (node (ref "C17") (pin "2") (pinfunction "2_2") (pintype "passive"))
      (node (ref "C18") (pin "2") (pinfunction "2_2") (pintype "passive"))
      (node (ref "C19") (pin "-") (pinfunction "-_-") (pintype "passive"))
      (node (ref "C2") (pin "2") (pinfunction "2_2") (pintype "passive"))
      (node (ref "C20") (pin "2") (pinfunction "2_2") (pintype "passive"))
      (node (ref "C21") (pin "+") (pinfunction "+_+") (pintype "passive"))
      (node (ref "C22") (pin "2") (pinfunction "2_2") (pintype "passive"))
      (node (ref "C23") (pin "2") (pinfunction "2_2") (pintype "passive"))
      (node (ref "C25") (pin "2") (pinfunction "2_2") (pintype "passive"))
      (node (ref "C26") (pin "2") (pinfunction "2_2") (pintype "passive"))
      (node (ref "C27") (pin "2") (pinfunction "2_2") (pintype "passive"))
      (node (ref "C28") (pin "1") (pinfunction "1_1") (pintype "passive"))
      (node (ref "C29") (pin "1") (pinfunction "1_1") (pintype "passive"))
      (node (ref "C3") (pin "2") (pinfunction "2_2") (pintype "passive"))
      (node (ref "C30") (pin "2") (pinfunction "2_2") (pintype "passive"))
      (node (ref "C31") (pin "2") (pinfunction "2_2") (pintype "passive"))
      (node (ref "C32") (pin "2") (pinfunction "2_2") (pintype "passive"))
      (node (ref "C33") (pin "1") (pinfunction "1_1") (pintype "passive"))
      (node (ref "C34") (pin "1") (pinfunction "1_1") (pintype "passive"))
      (node (ref "C4") (pin "2") (pinfunction "2_2") (pintype "passive"))
      (node (ref "C5") (pin "2") (pinfunction "2_2") (pintype "passive"))
      (node (ref "C6") (pin "2-") (pinfunction "2_2-") (pintype "passive"))
      (node (ref "C7") (pin "2") (pinfunction "2_2") (pintype "passive"))
      (node (ref "C8") (pin "2") (pinfunction "2_2") (pintype "passive"))
      (node (ref "C9") (pin "2") (pinfunction "2_2") (pintype "passive"))
      (node (ref "L2") (pin "P$2") (pinfunction "2_P$2") (pintype "passive"))
      (node (ref "LED1") (pin "K") (pinfunction "C_K") (pintype "passive"))
      (node (ref "R1") (pin "1") (pinfunction "1_1") (pintype "passive"))
      (node (ref "R14") (pin "1") (pinfunction "1_1") (pintype "passive"))
      (node (ref "R4") (pin "1") (pinfunction "1_1") (pintype "passive"))
      (node (ref "R7") (pin "2") (pinfunction "2_2") (pintype "passive"))
      (node (ref "R9") (pin "1") (pinfunction "1_1") (pintype "passive"))
      (node (ref "U$1") (pin "2_SLEEVE") (pinfunction "2_SLEEVE_2_SLEEVE") (pintype "bidirectional"))
      (node (ref "U$10") (pin "P$2") (pinfunction "2_GND_P$2") (pintype "bidirectional"))
      (node (ref "U$12") (pin "2") (pinfunction "2_GND_2") (pintype "bidirectional"))
      (node (ref "U$13") (pin "2") (pinfunction "2_GND_2") (pintype "bidirectional"))
      (node (ref "U$16") (pin "P$6") (pinfunction "6_GND_P$6") (pintype "bidirectional"))
      (node (ref "U$18") (pin "P$2") (pinfunction "2_VSS_P$2") (pintype "bidirectional"))
      (node (ref "U$19") (pin "A") (pinfunction "A_A") (pintype "bidirectional"))
      (node (ref "U$19") (pin "B") (pinfunction "B_B") (pintype "bidirectional"))
      (node (ref "U$20") (pin "1") (pinfunction "1_GND_1") (pintype "bidirectional"))
      (node (ref "U$22") (pin "1") (pinfunction "1_-VIN_1") (pintype "bidirectional"))
      (node (ref "U$22") (pin "6") (pinfunction "6_0V_6") (pintype "bidirectional"))
      (node (ref "U$3") (pin "A") (pinfunction "A_A") (pintype "bidirectional"))
      (node (ref "U$3") (pin "B") (pinfunction "B_B") (pintype "bidirectional"))
      (node (ref "U$6") (pin "3") (pinfunction "3_GND_3") (pintype "bidirectional"))
      (node (ref "U$7") (pin "2") (pinfunction "2_GND_2") (pintype "bidirectional"))
      (node (ref "U$74") (pin "A") (pinfunction "A_A") (pintype "bidirectional"))
      (node (ref "U$74") (pin "B") (pinfunction "B_B") (pintype "bidirectional"))
      (node (ref "U$75") (pin "A") (pinfunction "A_A") (pintype "bidirectional"))
      (node (ref "U$75") (pin "B") (pinfunction "B_B") (pintype "bidirectional"))
    )
    (net (code "14") (name "Net-(C22-Pad1)") (class "Default")
      (node (ref "C22") (pin "1") (pinfunction "1_1") (pintype "passive"))
      (node (ref "R6") (pin "2") (pinfunction "2_2") (pintype "passive"))
      (node (ref "R7") (pin "1") (pinfunction "1_1") (pintype "passive"))
    )
    (net (code "15") (name "Net-(L1-1)") (class "Default")
      (node (ref "D2") (pin "A") (pinfunction "A_A") (pintype "bidirectional"))
      (node (ref "L1") (pin "P$1") (pinfunction "1_P$1") (pintype "passive"))
      (node (ref "U$18") (pin "P$1") (pinfunction "1_LX_P$1") (pintype "bidirectional"))
    )
    (net (code "16") (name "Net-(L2-1)") (class "Default")
      (node (ref "D1") (pin "C") (pinfunction "C_C") (pintype "passive"))
      (node (ref "L2") (pin "P$1") (pinfunction "1_P$1") (pintype "passive"))
      (node (ref "U$16") (pin "P$7") (pinfunction "7_OUT_P$7") (pintype "bidirectional"))
    )
    (net (code "17") (name "Net-(LED1-PadA)") (class "Default")
      (node (ref "LED1") (pin "A") (pinfunction "A_A") (pintype "passive"))
      (node (ref "R2") (pin "1") (pinfunction "1_1") (pintype "passive"))
    )
    (net (code "18") (name "Net-(R11-Pad1)") (class "Default")
      (node (ref "R11") (pin "1") (pinfunction "1_1") (pintype "passive"))
      (node (ref "R12") (pin "2") (pinfunction "2_2") (pintype "passive"))
    )
    (net (code "19") (name "Net-(R13-Pad1)") (class "Default")
      (node (ref "R13") (pin "1") (pinfunction "1_1") (pintype "passive"))
      (node (ref "R14") (pin "2") (pinfunction "2_2") (pintype "passive"))
    )
    (net (code "20") (name "Net-(U$7-3_BP)") (class "Default")
      (node (ref "C8") (pin "1") (pinfunction "1_1") (pintype "passive"))
      (node (ref "U$7") (pin "3") (pinfunction "3_BP_3") (pintype "bidirectional"))
    )
    (net (code "21") (name "Net-(U$13-4_ADJ)") (class "Default")
      (node (ref "C15") (pin "2") (pinfunction "2_2") (pintype "passive"))
      (node (ref "R3") (pin "1") (pinfunction "1_1") (pintype "passive"))
      (node (ref "R4") (pin "2") (pinfunction "2_2") (pintype "passive"))
      (node (ref "U$13") (pin "4") (pinfunction "4_ADJ_4") (pintype "bidirectional"))
    )
    (net (code "22") (name "Net-(U$16-1_EN)") (class "Default")
      (node (ref "R5") (pin "1") (pinfunction "1_1") (pintype "passive"))
      (node (ref "U$16") (pin "P$1") (pinfunction "1_EN_P$1") (pintype "bidirectional"))
    )
    (net (code "23") (name "Net-(U$16-2_REF)") (class "Default")
      (node (ref "C18") (pin "1") (pinfunction "1_1") (pintype "passive"))
      (node (ref "R6") (pin "1") (pinfunction "1_1") (pintype "passive"))
      (node (ref "U$16") (pin "P$2") (pinfunction "2_REF_P$2") (pintype "bidirectional"))
    )
    (net (code "24") (name "Net-(U$16-4_COMP)") (class "Default")
      (node (ref "C23") (pin "1") (pinfunction "1_1") (pintype "passive"))
      (node (ref "U$16") (pin "P$4") (pinfunction "4_COMP_P$4") (pintype "bidirectional"))
    )
    (net (code "25") (name "Net-(U$18-3_FB)") (class "Default")
      (node (ref "C24") (pin "2") (pinfunction "2_2") (pintype "passive"))
      (node (ref "R8") (pin "1") (pinfunction "1_1") (pintype "passive"))
      (node (ref "R9") (pin "2") (pinfunction "2_2") (pintype "passive"))
      (node (ref "U$18") (pin "P$3") (pinfunction "3_FB_P$3") (pintype "bidirectional"))
    )
    (net (code "26") (name "Net-(U$18-4_CE{slash}SS)") (class "Default")
      (node (ref "C25") (pin "1") (pinfunction "1_1") (pintype "passive"))
      (node (ref "R10") (pin "1") (pinfunction "1_1") (pintype "passive"))
      (node (ref "U$18") (pin "P$4") (pinfunction "4_CE/SS_P$4") (pintype "bidirectional"))
    )
    (net (code "27") (name "Net-(U$20-3_EN)") (class "Default")
      (node (ref "R15") (pin "1") (pinfunction "1_1") (pintype "passive"))
      (node (ref "U$20") (pin "3") (pinfunction "3_EN_3") (pintype "bidirectional"))
    )
    (net (code "28") (name "Net-(U$20-4_FB)") (class "Default")
      (node (ref "R12") (pin "1") (pinfunction "1_1") (pintype "passive"))
      (node (ref "R13") (pin "2") (pinfunction "2_2") (pintype "passive"))
      (node (ref "U$20") (pin "4") (pinfunction "4_FB_4") (pintype "bidirectional"))
    )
    (net (code "29") (name "Net-(U$22-8_+VIN)") (class "Default")
      (node (ref "L3") (pin "2") (pinfunction "2_2") (pintype "passive"))
      (node (ref "U$22") (pin "8") (pinfunction "8_+VIN_8") (pintype "bidirectional"))
    )
    (net (code "30") (name "V+3V") (class "Default")
      (node (ref "C12") (pin "1") (pinfunction "1_1") (pintype "passive"))
      (node (ref "U$10") (pin "P$5") (pinfunction "5_OUT_P$5") (pintype "bidirectional"))
      (node (ref "U$11") (pin "A") (pinfunction "A_A") (pintype "bidirectional"))
      (node (ref "U$11") (pin "B") (pinfunction "B_B") (pintype "bidirectional"))
    )
    (net (code "31") (name "V-5V_2") (class "Default")
      (node (ref "C33") (pin "2") (pinfunction "2_2") (pintype "passive"))
      (node (ref "C34") (pin "2") (pinfunction "2_2") (pintype "passive"))
      (node (ref "U$22") (pin "3") (pinfunction "3_-VOUT_3") (pintype "bidirectional"))
      (node (ref "U$22") (pin "4") (pinfunction "4_-VOUT_4") (pintype "bidirectional"))
      (node (ref "U$23") (pin "A") (pinfunction "A_A") (pintype "bidirectional"))
      (node (ref "U$23") (pin "B") (pinfunction "B_B") (pintype "bidirectional"))
    )
    (net (code "32") (name "V_2P5") (class "Default")
      (node (ref "C10") (pin "1") (pinfunction "1_1") (pintype "passive"))
      (node (ref "U$7") (pin "1") (pinfunction "1_OUTB_1") (pintype "bidirectional"))
      (node (ref "U$8") (pin "A") (pinfunction "A_A") (pintype "bidirectional"))
      (node (ref "U$8") (pin "B") (pinfunction "B_B") (pintype "bidirectional"))
    )
    (net (code "33") (name "unconnected-(U$10-4_NC-PadP$4)") (class "Default")
      (node (ref "U$10") (pin "P$4") (pinfunction "4_NC_P$4") (pintype "bidirectional"))
    )
    (net (code "34") (name "unconnected-(U$12-4_NC-Pad4)") (class "Default")
      (node (ref "U$12") (pin "4") (pinfunction "4_NC_4") (pintype "bidirectional"))
    )
    (net (code "35") (name "unconnected-(U$16-3_SS-PadP$3)") (class "Default")
      (node (ref "U$16") (pin "P$3") (pinfunction "3_SS_P$3") (pintype "bidirectional"))
    )
    (net (code "36") (name "unconnected-(U$22-2_NA-Pad2)") (class "Default")
      (node (ref "U$22") (pin "2") (pinfunction "2_NA_2") (pintype "bidirectional"))
    )
    (net (code "37") (name "unconnected-(U$22-7_NC-Pad7)") (class "Default")
      (node (ref "U$22") (pin "7") (pinfunction "7_NC_7") (pintype "bidirectional"))
    )
  )
)
